# CPU.net
KiCad netlist of a schematic drawn in Altium Designer
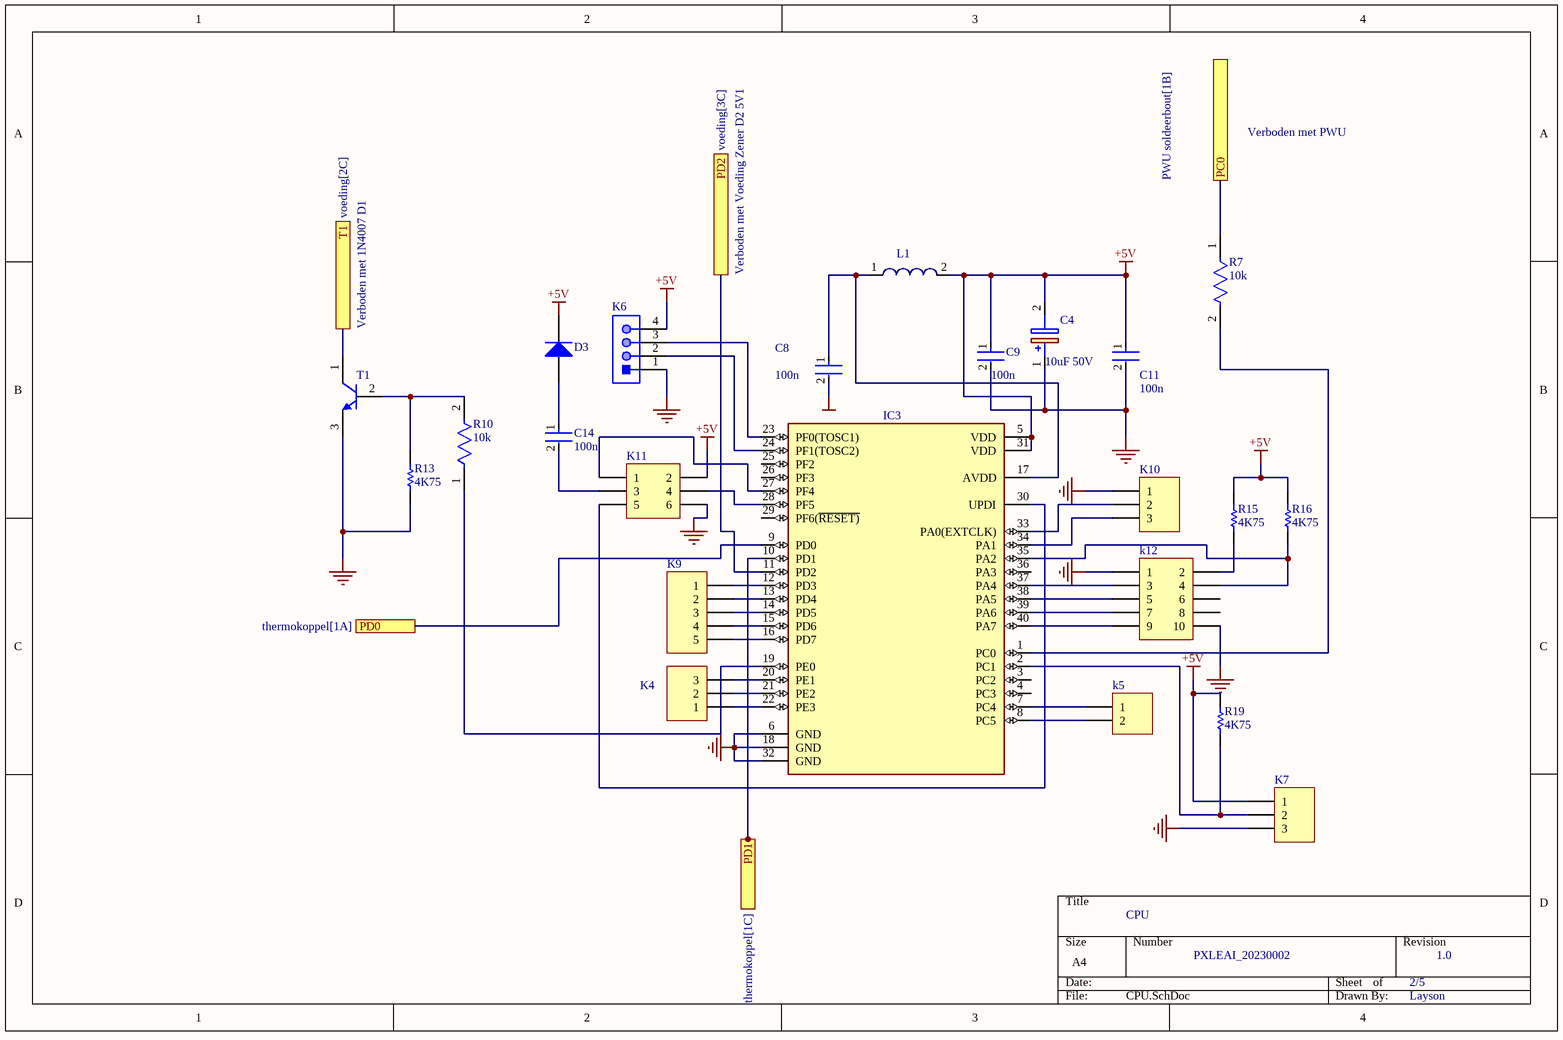
[diagram p0: CPU.SchDoc]

(export (version "E")
  (design (tool "Eeschema 10.0.6"))
  (components
    (comp (ref "C4")
      (value "10uF 50V")
      (footprint "SamacSys:CAPPRD200W52D525H1200")
      (description "Capacitor Polarised\r\nMCGPR50V106M5X11")
      (fields (field (name "MANUFACTURER_PART_NUMBER") "MCGPR50V106M5X11"))
      (libsource (lib "*") (part "MCGPR50V106M5X11"))
    )
    (comp (ref "C8")
      (value "100n")
      (footprint "FP-C0402-BB-MFG")
      (description "CAP CER 0.1UF 10V X5R 0402")
      (fields (field (name "MANUFACTURER") "Kemet") (field (name "TOLERANCE") "0.1"))
      (libsource (lib "Altium Content Vault") (part "b4654b650e69147ec39a6b967a45e02"))
    )
    (comp (ref "C9")
      (value "100n")
      (footprint "FP-C0402-BB-MFG")
      (description "CAP CER 0.1UF 10V X5R 0402")
      (fields (field (name "MANUFACTURER") "Kemet") (field (name "TOLERANCE") "0.1"))
      (libsource (lib "Altium Content Vault") (part "b4654b650e69147ec39a6b967a45e02"))
    )
    (comp (ref "C11")
      (value "100n")
      (footprint "FP-C0402-BB-MFG")
      (description "CAP CER 0.1UF 10V X5R 0402")
      (fields (field (name "MANUFACTURER") "Kemet") (field (name "TOLERANCE") "0.1"))
      (libsource (lib "Altium Content Vault") (part "b4654b650e69147ec39a6b967a45e02"))
    )
    (comp (ref "C14")
      (value "100n")
      (footprint "FP-C0402-BB-MFG")
      (description "CAP CER 0.1UF 10V X5R 0402")
      (fields (field (name "MANUFACTURER") "Kemet") (field (name "TOLERANCE") "0.1"))
      (libsource (lib "Altium Content Vault") (part "b4654b650e69147ec39a6b967a45e02"))
    )
    (comp (ref "D3")
      (value "Diode 1N4148")
      (footprint "DO-35")
      (description "High Conductance Fast Diode")
      (fields (field (name "PUBLISHER") "Altium Limited"))
      (libsource (lib "Miscellaneous Devices") (part "Diode 1N4148"))
    )
    (comp (ref "IC3")
      (value "ATMEGA4809-PF")
      (footprint "FP-C04-016-MFG")
      (description "IC MCU 8BIT 48KB FLASH 40DIP")
      (libsource (lib "Altium Content Vault") (part "0f7c9a3d00f44248c37109e18f8a0f0"))
    )
    (comp (ref "K4")
      (value "Header 3")
      (footprint "HDR1X3")
      (description "Header, 3-Pin")
      (fields (field (name "PUBLISHER") "Altium Limited"))
      (libsource (lib "") (part "Header 3_1"))
    )
    (comp (ref "k5")
      (value "Header 2")
      (footprint "HDR1X2")
      (description "Header, 2-Pin")
      (fields (field (name "PUBLISHER") "Altium Limited"))
      (libsource (lib "Miscellaneous Connectors") (part "Header 2"))
    )
    (comp (ref "K6")
      (value "66200411122")
      (footprint "66200411122")
      (description "THT Male Header WR-MPC3, Vertical, Single Row, pitch 3 mm, 4 pins")
      (fields (field (name "MANUFACTURER") "Wurth Elektronik") (field (name "PUBLISHER") "WurthElektronik"))
      (libsource (lib "Altium Content Vault") (part "WE-CN-1P-M-R4"))
    )
    (comp (ref "K7")
      (value "Header 3")
      (footprint "HDR1X3")
      (description "Header, 3-Pin")
      (fields (field (name "PUBLISHER") "Altium Limited"))
      (libsource (lib "Miscellaneous Connectors") (part "Header 3"))
    )
    (comp (ref "K9")
      (value "Header 5")
      (footprint "HDR1X5")
      (description "Header, 5-Pin")
      (fields (field (name "PUBLISHER") "Altium Limited"))
      (libsource (lib "Miscellaneous Connectors") (part "Header 5"))
    )
    (comp (ref "K10")
      (value "Header 3")
      (footprint "HDR1X3")
      (description "Header, 3-Pin")
      (fields (field (name "PUBLISHER") "Altium Limited"))
      (libsource (lib "Miscellaneous Connectors") (part "Header 3"))
    )
    (comp (ref "K11")
      (value "MHDR2X3")
      (footprint "MHDR2X3")
      (description "Header, 3-Pin, Dual row")
      (fields (field (name "PUBLISHER") "Altium Limited"))
      (libsource (lib "Miscellaneous Connectors") (part "MHDR2X3"))
    )
    (comp (ref "k12")
      (value "Header 5X2")
      (footprint "HDR2X5")
      (description "Header, 5-Pin, Dual row")
      (fields (field (name "PUBLISHER") "Altium Limited"))
      (libsource (lib "Miscellaneous Connectors") (part "Header 5X2"))
    )
    (comp (ref "L1")
      (value "760308201")
      (footprint "3737")
      (description "Wireless Power Charging Coil  WE-WPCC, L=10.0 µH")
      (fields (field (name "MANUFACTURER") "Wuerth Elektronik"))
      (libsource (lib "Altium Content Vault") (part "WE-IND-INDUCTOR-2"))
    )
    (comp (ref "R7")
      (value "10k")
      (footprint "FP-MBB0207-MFG")
      (description "RES 10K OHM 0.6W 1% AXIAL")
      (fields (field (name "TOLERANCE") "1%"))
      (libsource (lib "Altium Content Vault") (part "1029c3af85768c4190bb7ad29bc67b5"))
    )
    (comp (ref "R10")
      (value "10k")
      (footprint "FP-MBB0207-MFG")
      (description "RES 10K OHM 0.6W 1% AXIAL")
      (fields (field (name "TOLERANCE") "1%"))
      (libsource (lib "Altium Content Vault") (part "1029c3af85768c4190bb7ad29bc67b5"))
    )
    (comp (ref "R13")
      (value "4K75")
      (footprint "RESA60-630X240")
      (description "Axial Resistor, 4.75 KOhm, +/- 1%, 0.25 W, -55 to 155 degC, 2-Pin THD, RoHS, Bulk")
      (fields (field (name "TOLERANCE") "10%"))
      (libsource (lib "Altium Content Vault") (part "RES-2"))
    )
    (comp (ref "R15")
      (value "4K75")
      (footprint "RESA60-630X240")
      (description "Axial Resistor, 4.75 KOhm, +/- 1%, 0.25 W, -55 to 155 degC, 2-Pin THD, RoHS, Bulk")
      (fields (field (name "TOLERANCE") "10%"))
      (libsource (lib "Altium Content Vault") (part "RES-2"))
    )
    (comp (ref "R16")
      (value "4K75")
      (footprint "RESA60-630X240")
      (description "Axial Resistor, 4.75 KOhm, +/- 1%, 0.25 W, -55 to 155 degC, 2-Pin THD, RoHS, Bulk")
      (fields (field (name "TOLERANCE") "10%"))
      (libsource (lib "Altium Content Vault") (part "RES-2"))
    )
    (comp (ref "R19")
      (value "4K75")
      (footprint "RESA60-630X240")
      (description "Axial Resistor, 4.75 KOhm, +/- 1%, 0.25 W, -55 to 155 degC, 2-Pin THD, RoHS, Bulk")
      (fields (field (name "TOLERANCE") "10%"))
      (libsource (lib "Altium Content Vault") (part "RES-2"))
    )
    (comp (ref "T1")
      (value "BC547CZL1G")
      (footprint "ONSC-TO-92-3-29-11_AM_BL")
      (description "Amplifier Transistor, NPN Silicon, 3-Pin TO-92, Pb-Free, Ammo Box")
      (fields (field (name "MANUFACTURER") "On Semiconductor"))
      (libsource (lib "Altium Content Vault") (part "ONSC-NPN-C1B2E3-3"))
    )
  )
  (nets
    (net (code "1") (name "+5V") (class "Default")
      (node (ref "C11") (pin "1") (pinfunction "1_1") (pintype "passive"))
      (node (ref "C4") (pin "2") (pinfunction "-_2") (pintype "passive"))
      (node (ref "C9") (pin "1") (pinfunction "1_1") (pintype "passive"))
      (node (ref "D3") (pin "2") (pinfunction "K_2") (pintype "passive"))
      (node (ref "IC3") (pin "31") (pinfunction "VDD_31") (pintype "power_in"))
      (node (ref "IC3") (pin "5") (pinfunction "VDD_5") (pintype "power_in"))
      (node (ref "K11") (pin "2") (pinfunction "2_2") (pintype "passive"))
      (node (ref "K6") (pin "4") (pinfunction "4_4") (pintype "passive"))
      (node (ref "K7") (pin "1") (pinfunction "1_1") (pintype "passive"))
      (node (ref "L1") (pin "2") (pinfunction "2_2") (pintype "passive"))
      (node (ref "R15") (pin "2") (pinfunction "2_2") (pintype "passive"))
      (node (ref "R16") (pin "2") (pinfunction "2_2") (pintype "passive"))
      (node (ref "R19") (pin "2") (pinfunction "2_2") (pintype "passive"))
    )
    (net (code "2") (name "/PC0") (class "Default")
      (node (ref "R7") (pin "1") (pinfunction "1_1") (pintype "passive"))
    )
    (net (code "3") (name "/PD0") (class "Default")
      (node (ref "IC3") (pin "9") (pinfunction "PD0_9") (pintype "bidirectional"))
    )
    (net (code "4") (name "/PD1") (class "Default")
      (node (ref "IC3") (pin "10") (pinfunction "PD1_10") (pintype "bidirectional"))
    )
    (net (code "5") (name "/PD2") (class "Default")
      (node (ref "IC3") (pin "11") (pinfunction "PD2_11") (pintype "bidirectional"))
    )
    (net (code "6") (name "/T1") (class "Default")
      (node (ref "T1") (pin "1") (pinfunction "C_1") (pintype "passive"))
    )
    (net (code "7") (name "GND") (class "Default")
      (node (ref "C11") (pin "2") (pinfunction "2_2") (pintype "passive"))
      (node (ref "C4") (pin "1") (pinfunction "+_1") (pintype "passive"))
      (node (ref "C8") (pin "2") (pinfunction "2_2") (pintype "passive"))
      (node (ref "C9") (pin "2") (pinfunction "2_2") (pintype "passive"))
      (node (ref "IC3") (pin "18") (pinfunction "GND_18") (pintype "power_in"))
      (node (ref "IC3") (pin "32") (pinfunction "GND_32") (pintype "power_in"))
      (node (ref "IC3") (pin "6") (pinfunction "GND_6") (pintype "power_in"))
      (node (ref "K10") (pin "1") (pinfunction "1_1") (pintype "passive"))
      (node (ref "K11") (pin "6") (pinfunction "6_6") (pintype "passive"))
      (node (ref "K6") (pin "1") (pinfunction "1_1") (pintype "passive"))
      (node (ref "K7") (pin "3") (pinfunction "3_3") (pintype "passive"))
      (node (ref "R13") (pin "1") (pinfunction "1_1") (pintype "passive"))
      (node (ref "T1") (pin "3") (pinfunction "E_3") (pintype "passive"))
      (node (ref "k12") (pin "1") (pinfunction "1_1") (pintype "passive"))
      (node (ref "k12") (pin "10") (pinfunction "10_10") (pintype "passive"))
    )
    (net (code "8") (name "Net-(C14-Pad2)") (class "Default")
      (node (ref "C14") (pin "2") (pinfunction "2_2") (pintype "passive"))
      (node (ref "K11") (pin "3") (pinfunction "3_3") (pintype "passive"))
    )
    (net (code "9") (name "Net-(D3-A)") (class "Default")
      (node (ref "C14") (pin "1") (pinfunction "1_1") (pintype "passive"))
      (node (ref "D3") (pin "1") (pinfunction "A_1") (pintype "passive"))
    )
    (net (code "10") (name "Net-(IC3-AVDD)") (class "Default")
      (node (ref "C8") (pin "1") (pinfunction "1_1") (pintype "passive"))
      (node (ref "IC3") (pin "17") (pinfunction "AVDD_17") (pintype "power_in"))
      (node (ref "L1") (pin "1") (pinfunction "1_1") (pintype "passive"))
    )
    (net (code "11") (name "Net-(IC3-PA0(EXTCLK))") (class "Default")
      (node (ref "IC3") (pin "33") (pinfunction "PA0(EXTCLK)_33") (pintype "bidirectional"))
      (node (ref "K10") (pin "2") (pinfunction "2_2") (pintype "passive"))
    )
    (net (code "12") (name "Net-(IC3-PA1)") (class "Default")
      (node (ref "IC3") (pin "34") (pinfunction "PA1_34") (pintype "bidirectional"))
      (node (ref "K10") (pin "3") (pinfunction "3_3") (pintype "passive"))
    )
    (net (code "13") (name "Net-(IC3-PA2)") (class "Default")
      (node (ref "IC3") (pin "35") (pinfunction "PA2_35") (pintype "bidirectional"))
      (node (ref "R16") (pin "1") (pinfunction "1_1") (pintype "passive"))
      (node (ref "k12") (pin "4") (pinfunction "4_4") (pintype "passive"))
    )
    (net (code "14") (name "Net-(IC3-PA4)") (class "Default")
      (node (ref "IC3") (pin "37") (pinfunction "PA4_37") (pintype "bidirectional"))
      (node (ref "k12") (pin "3") (pinfunction "3_3") (pintype "passive"))
    )
    (net (code "15") (name "Net-(IC3-PA5)") (class "Default")
      (node (ref "IC3") (pin "38") (pinfunction "PA5_38") (pintype "bidirectional"))
      (node (ref "k12") (pin "5") (pinfunction "5_5") (pintype "passive"))
    )
    (net (code "16") (name "Net-(IC3-PA6)") (class "Default")
      (node (ref "IC3") (pin "39") (pinfunction "PA6_39") (pintype "bidirectional"))
      (node (ref "k12") (pin "7") (pinfunction "7_7") (pintype "passive"))
    )
    (net (code "17") (name "Net-(IC3-PA7)") (class "Default")
      (node (ref "IC3") (pin "40") (pinfunction "PA7_40") (pintype "bidirectional"))
      (node (ref "k12") (pin "9") (pinfunction "9_9") (pintype "passive"))
    )
    (net (code "18") (name "Net-(IC3-PC0)") (class "Default")
      (node (ref "IC3") (pin "1") (pinfunction "PC0_1") (pintype "bidirectional"))
      (node (ref "R7") (pin "2") (pinfunction "2_2") (pintype "passive"))
    )
    (net (code "19") (name "Net-(IC3-PC1)") (class "Default")
      (node (ref "IC3") (pin "2") (pinfunction "PC1_2") (pintype "bidirectional"))
      (node (ref "K7") (pin "2") (pinfunction "2_2") (pintype "passive"))
      (node (ref "R19") (pin "1") (pinfunction "1_1") (pintype "passive"))
    )
    (net (code "20") (name "Net-(IC3-PC4)") (class "Default")
      (node (ref "IC3") (pin "7") (pinfunction "PC4_7") (pintype "bidirectional"))
      (node (ref "k5") (pin "1") (pinfunction "1_1") (pintype "passive"))
    )
    (net (code "21") (name "Net-(IC3-PC5)") (class "Default")
      (node (ref "IC3") (pin "8") (pinfunction "PC5_8") (pintype "bidirectional"))
      (node (ref "k5") (pin "2") (pinfunction "2_2") (pintype "passive"))
    )
    (net (code "22") (name "Net-(IC3-PD3)") (class "Default")
      (node (ref "IC3") (pin "12") (pinfunction "PD3_12") (pintype "bidirectional"))
      (node (ref "K9") (pin "1") (pinfunction "1_1") (pintype "passive"))
    )
    (net (code "23") (name "Net-(IC3-PD4)") (class "Default")
      (node (ref "IC3") (pin "13") (pinfunction "PD4_13") (pintype "bidirectional"))
      (node (ref "K9") (pin "2") (pinfunction "2_2") (pintype "passive"))
    )
    (net (code "24") (name "Net-(IC3-PD5)") (class "Default")
      (node (ref "IC3") (pin "14") (pinfunction "PD5_14") (pintype "bidirectional"))
      (node (ref "K9") (pin "3") (pinfunction "3_3") (pintype "passive"))
    )
    (net (code "25") (name "Net-(IC3-PD6)") (class "Default")
      (node (ref "IC3") (pin "15") (pinfunction "PD6_15") (pintype "bidirectional"))
      (node (ref "K9") (pin "4") (pinfunction "4_4") (pintype "passive"))
    )
    (net (code "26") (name "Net-(IC3-PD7)") (class "Default")
      (node (ref "IC3") (pin "16") (pinfunction "PD7_16") (pintype "bidirectional"))
      (node (ref "K9") (pin "5") (pinfunction "5_5") (pintype "passive"))
    )
    (net (code "27") (name "Net-(IC3-PE0)") (class "Default")
      (node (ref "IC3") (pin "19") (pinfunction "PE0_19") (pintype "bidirectional"))
      (node (ref "R10") (pin "1") (pinfunction "1_1") (pintype "passive"))
    )
    (net (code "28") (name "Net-(IC3-PE1)") (class "Default")
      (node (ref "IC3") (pin "20") (pinfunction "PE1_20") (pintype "bidirectional"))
      (node (ref "K4") (pin "3") (pinfunction "3_3") (pintype "passive"))
    )
    (net (code "29") (name "Net-(IC3-PE2)") (class "Default")
      (node (ref "IC3") (pin "21") (pinfunction "PE2_21") (pintype "bidirectional"))
      (node (ref "K4") (pin "2") (pinfunction "2_2") (pintype "passive"))
    )
    (net (code "30") (name "Net-(IC3-PE3)") (class "Default")
      (node (ref "IC3") (pin "22") (pinfunction "PE3_22") (pintype "bidirectional"))
      (node (ref "K4") (pin "1") (pinfunction "1_1") (pintype "passive"))
    )
    (net (code "31") (name "Net-(IC3-PF0(TOSC1))") (class "Default")
      (node (ref "IC3") (pin "23") (pinfunction "PF0(TOSC1)_23") (pintype "bidirectional"))
      (node (ref "K6") (pin "3") (pinfunction "3_3") (pintype "passive"))
    )
    (net (code "32") (name "Net-(IC3-PF1(TOSC2))") (class "Default")
      (node (ref "IC3") (pin "24") (pinfunction "PF1(TOSC2)_24") (pintype "bidirectional"))
      (node (ref "K6") (pin "2") (pinfunction "2_2") (pintype "passive"))
    )
    (net (code "33") (name "Net-(IC3-PF4)") (class "Default")
      (node (ref "IC3") (pin "27") (pinfunction "PF4_27") (pintype "bidirectional"))
      (node (ref "K11") (pin "1") (pinfunction "1_1") (pintype "passive"))
    )
    (net (code "34") (name "Net-(IC3-PF5)") (class "Default")
      (node (ref "IC3") (pin "28") (pinfunction "PF5_28") (pintype "bidirectional"))
      (node (ref "K11") (pin "4") (pinfunction "4_4") (pintype "passive"))
    )
    (net (code "35") (name "Net-(IC3-UPDI)") (class "Default")
      (node (ref "IC3") (pin "30") (pinfunction "UPDI_30") (pintype "passive"))
      (node (ref "K11") (pin "5") (pinfunction "5_5") (pintype "passive"))
    )
    (net (code "36") (name "Net-(R15-Pad1)") (class "Default")
      (node (ref "R15") (pin "1") (pinfunction "1_1") (pintype "passive"))
      (node (ref "k12") (pin "2") (pinfunction "2_2") (pintype "passive"))
    )
    (net (code "37") (name "Net-(T1-B)") (class "Default")
      (node (ref "R10") (pin "2") (pinfunction "2_2") (pintype "passive"))
      (node (ref "R13") (pin "2") (pinfunction "2_2") (pintype "passive"))
      (node (ref "T1") (pin "2") (pinfunction "B_2") (pintype "passive"))
    )
    (net (code "38") (name "unconnected-(IC3-PA3-Pad36)") (class "Default")
      (node (ref "IC3") (pin "36") (pinfunction "PA3_36") (pintype "bidirectional"))
    )
    (net (code "39") (name "unconnected-(IC3-PC2-Pad3)") (class "Default")
      (node (ref "IC3") (pin "3") (pinfunction "PC2_3") (pintype "bidirectional"))
    )
    (net (code "40") (name "unconnected-(IC3-PC3-Pad4)") (class "Default")
      (node (ref "IC3") (pin "4") (pinfunction "PC3_4") (pintype "bidirectional"))
    )
    (net (code "41") (name "unconnected-(IC3-PF2-Pad25)") (class "Default")
      (node (ref "IC3") (pin "25") (pinfunction "PF2_25") (pintype "bidirectional"))
    )
    (net (code "42") (name "unconnected-(IC3-PF3-Pad26)") (class "Default")
      (node (ref "IC3") (pin "26") (pinfunction "PF3_26") (pintype "bidirectional"))
    )
    (net (code "43") (name "unconnected-(IC3-PF6(~{RESET)}-Pad29)") (class "Default")
      (node (ref "IC3") (pin "29") (pinfunction "PF6(~{RESET)}_29") (pintype "bidirectional"))
    )
    (net (code "44") (name "unconnected-(k12-Pad6)") (class "Default")
      (node (ref "k12") (pin "6") (pinfunction "6_6") (pintype "passive"))
    )
    (net (code "45") (name "unconnected-(k12-Pad8)") (class "Default")
      (node (ref "k12") (pin "8") (pinfunction "8_8") (pintype "passive"))
    )
  )
)
